# Main.net
KiCad netlist of a schematic drawn in Altium Designer
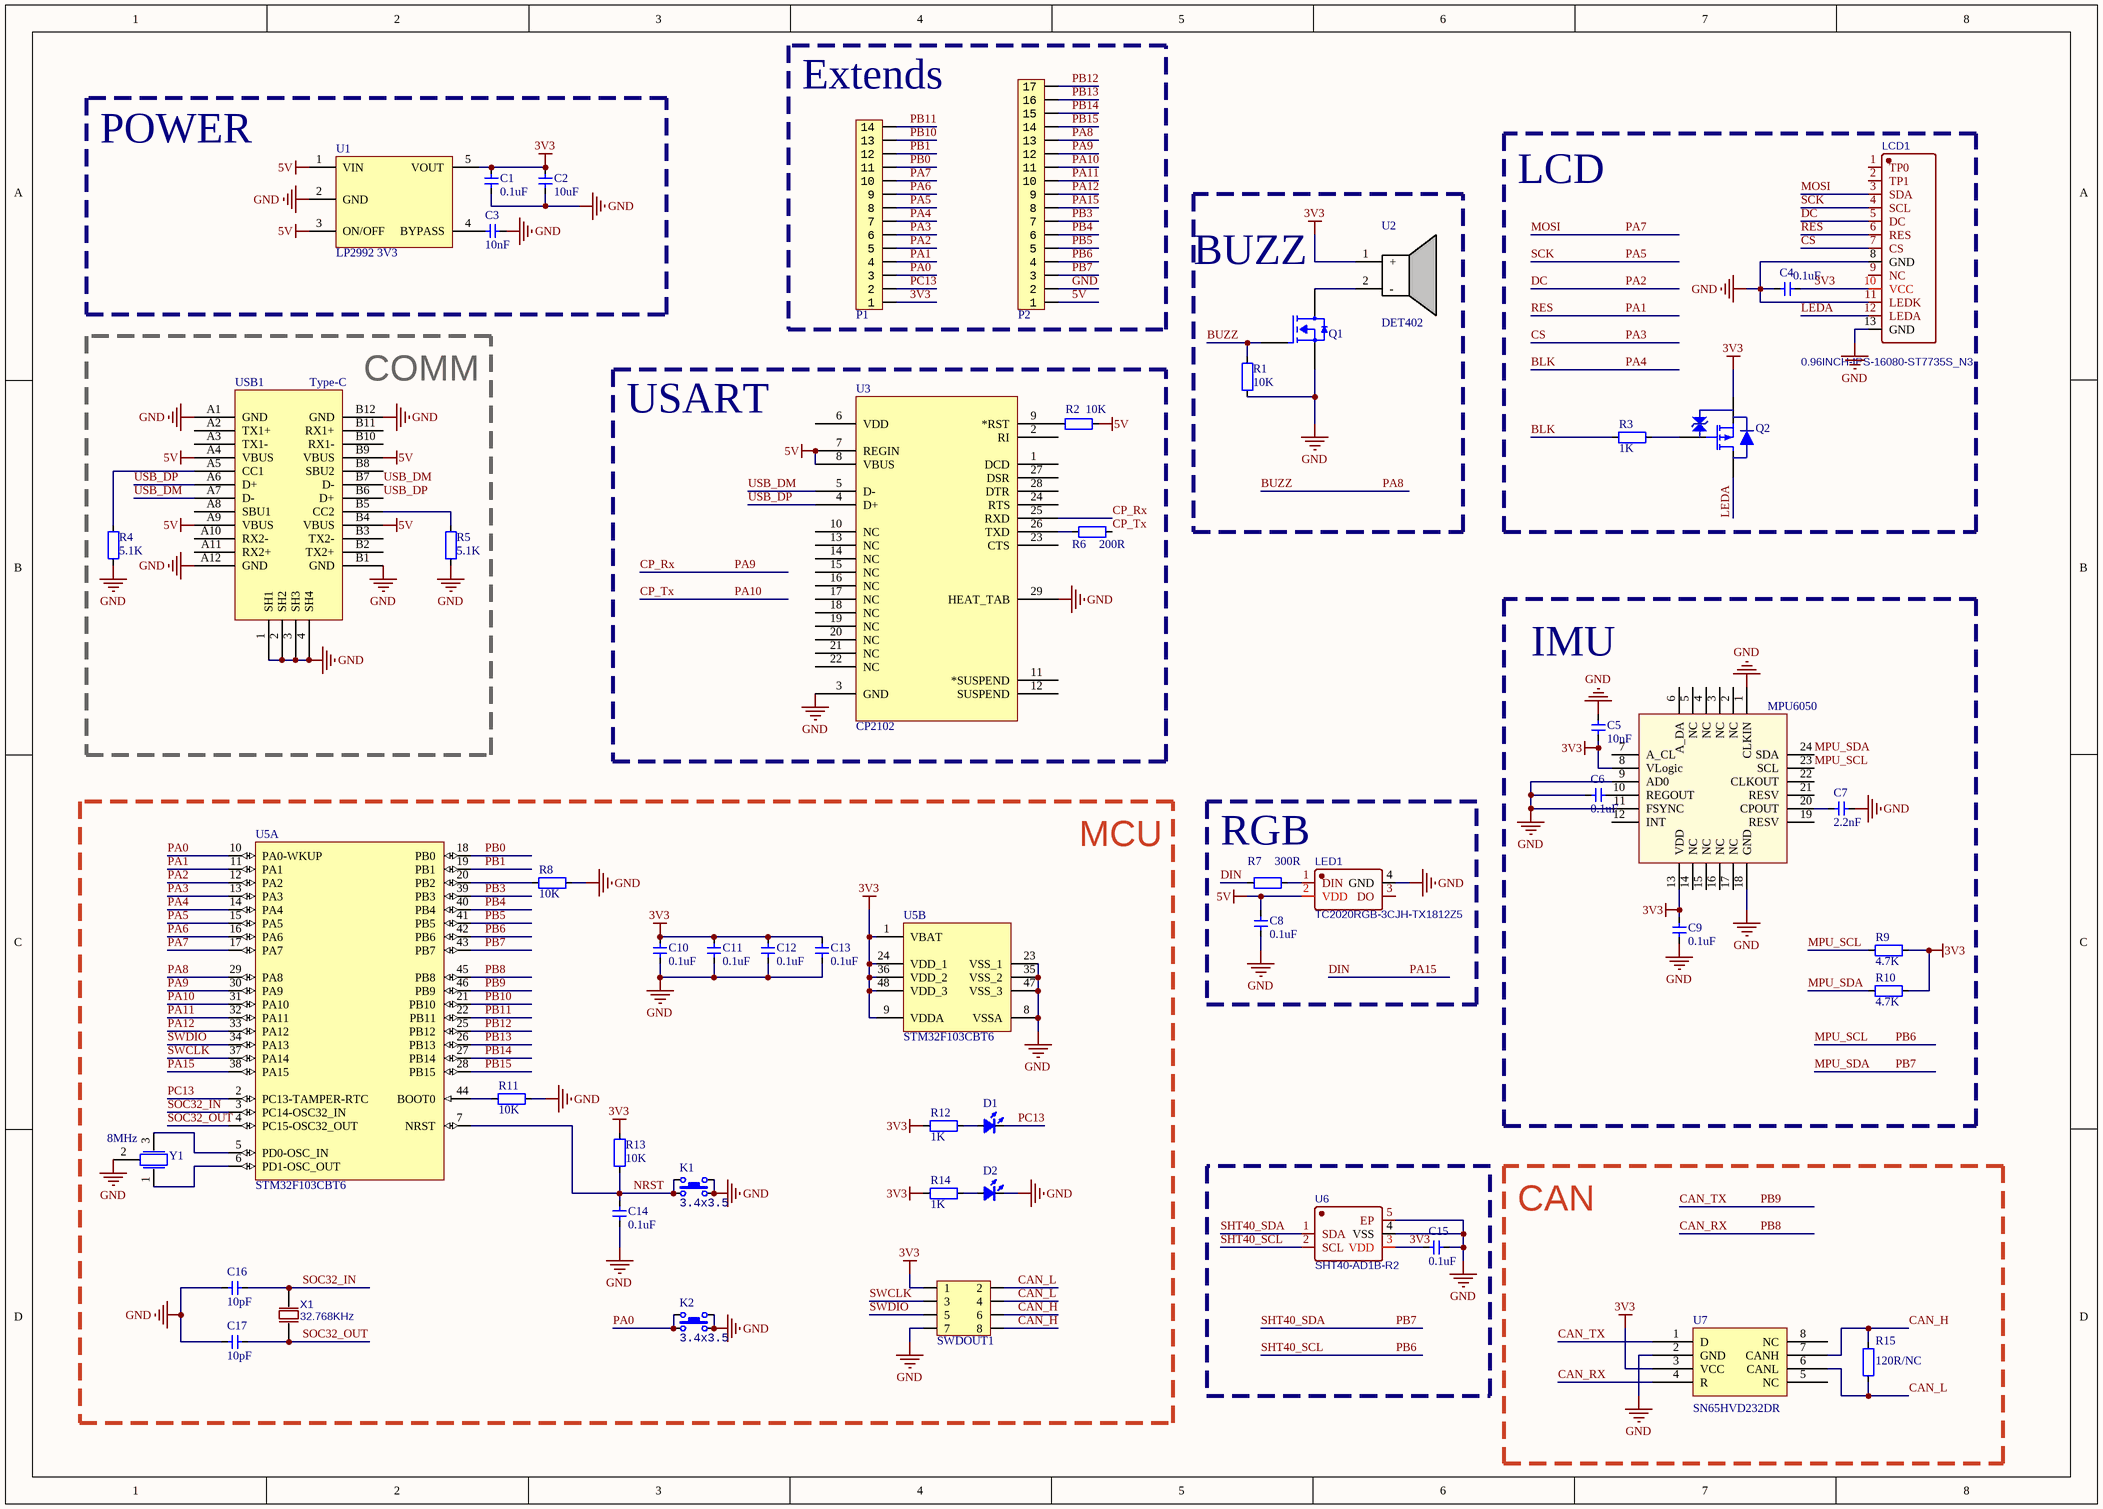
[diagram p0: Main.SchDoc]

(export (version "E")
  (design (tool "Eeschema 10.0.6"))
  (components
    (comp (ref "C1")
      (value "0.1uF")
      (footprint "CAP_0402")
      (description "Capacitor")
      (libsource (lib "MyPcbLib") (part "电容-0402"))
    )
    (comp (ref "C2")
      (value "10uF")
      (footprint "CAP_0402")
      (description "Capacitor")
      (libsource (lib "MyPcbLib") (part "电容-0402"))
    )
    (comp (ref "C3")
      (value "10nF")
      (footprint "CAP_0402")
      (description "Capacitor")
      (libsource (lib "MyPcbLib") (part "电容-0402"))
    )
    (comp (ref "C4")
      (value "0.1uF")
      (footprint "CAP_0402")
      (description "Capacitor")
      (libsource (lib "MyPcbLib") (part "电容-0402"))
    )
    (comp (ref "C5")
      (value "10nF")
      (footprint "CAP_0402")
      (description "Capacitor")
      (libsource (lib "MyPcbLib") (part "电容-0402"))
    )
    (comp (ref "C6")
      (value "0.1uF")
      (footprint "CAP_0402")
      (description "Capacitor")
      (libsource (lib "MyPcbLib") (part "电容-0402"))
    )
    (comp (ref "C7")
      (value "2.2nF")
      (footprint "CAP_0402")
      (description "Capacitor")
      (libsource (lib "MyPcbLib") (part "电容-0402"))
    )
    (comp (ref "C8")
      (value "0.1uF")
      (footprint "CAP_0402")
      (description "Capacitor")
      (libsource (lib "MyPcbLib") (part "电容-0402"))
    )
    (comp (ref "C9")
      (value "0.1uF")
      (footprint "CAP_0402")
      (description "Capacitor")
      (libsource (lib "MyPcbLib") (part "电容-0402"))
    )
    (comp (ref "C10")
      (value "0.1uF")
      (footprint "CAP_0402")
      (description "Capacitor")
      (libsource (lib "MyPcbLib") (part "电容-0402"))
    )
    (comp (ref "C11")
      (value "0.1uF")
      (footprint "CAP_0402")
      (description "Capacitor")
      (libsource (lib "MyPcbLib") (part "电容-0402"))
    )
    (comp (ref "C12")
      (value "0.1uF")
      (footprint "CAP_0402")
      (description "Capacitor")
      (libsource (lib "MyPcbLib") (part "电容-0402"))
    )
    (comp (ref "C13")
      (value "0.1uF")
      (footprint "CAP_0402")
      (description "Capacitor")
      (libsource (lib "MyPcbLib") (part "电容-0402"))
    )
    (comp (ref "C14")
      (value "0.1uF")
      (footprint "CAP_0402")
      (description "Capacitor")
      (libsource (lib "MyPcbLib") (part "电容-0402"))
    )
    (comp (ref "C15")
      (value "0.1uF")
      (footprint "CAP_0402")
      (description "Capacitor")
      (libsource (lib "MyPcbLib") (part "电容-0402"))
    )
    (comp (ref "C16")
      (value "10pF")
      (footprint "CAP_0402")
      (description "Capacitor")
      (libsource (lib "MyPcbLib") (part "电容-0402"))
    )
    (comp (ref "C17")
      (value "10pF")
      (footprint "CAP_0402")
      (description "Capacitor")
      (libsource (lib "MyPcbLib") (part "电容-0402"))
    )
    (comp (ref "D1")
      (value "color?")
      (footprint "LED_0402_RED")
      (description "LED")
      (libsource (lib "KitSprout") (part "LED_0402"))
    )
    (comp (ref "D2")
      (value "color?")
      (footprint "LED_0402_RED")
      (description "LED")
      (libsource (lib "KitSprout") (part "LED_0402"))
    )
    (comp (ref "K1")
      (value "3.4x3.5")
      (footprint "ButtonTACT_3.5*3.55_90")
      (description "Button")
      (fields (field (name "Comment") "TACT 4P"))
      (libsource (lib "KitSprout") (part "ButtonTACT"))
    )
    (comp (ref "K2")
      (value "3.4x3.5")
      (footprint "ButtonTACT_3.5*3.55_90")
      (description "Button")
      (fields (field (name "Comment") "TACT 4P"))
      (libsource (lib "KitSprout") (part "ButtonTACT"))
    )
    (comp (ref "LCD1")
      (value "0.96INCH-IPS-16080-ST7735S_N3")
      (footprint "LCD-0.96INCH-IPS-TFT-16080-ST7735S")
      (fields (field (name "CONTRIBUTOR") "micespring"))
      (libsource (lib "0.96 TFT") (part "0.96INCH-IPS-16080-ST7735S_N3"))
    )
    (comp (ref "LED1")
      (value "TC2020RGB-3CJH-TX1812Z5")
      (footprint "LED-SMD_4P-L2.1-W2.1-TL_TC2020RGB")
      (fields (field (name "BOM_SUPPLIER PART") "C784564") (field (name "CONTRIBUTOR") "LCSC"))
      (libsource (lib "GraduationProject") (part "TC2020RGB-3CJH-TX1812Z5"))
    )
    (comp (ref "P1")
      (value "HDR1x14_2.54")
      (footprint "HDR1X14_2.54_180")
      (description "Header")
      (libsource (lib "ESP32-PicoDK 12") (part "HDR1x14_2.54"))
    )
    (comp (ref "P2")
      (value "HDR1x17_2.54")
      (footprint "HDR1X17_2.54_180")
      (description "Header")
      (libsource (lib "ESP32-PicoDK") (part "HDR1x17_2.54"))
    )
    (comp (ref "Q1")
      (value "AO3400A")
      (footprint "SOT23-3")
      (description "N-MOS")
      (libsource (lib "Controller") (part "AO3400A"))
    )
    (comp (ref "Q2")
      (value "AO3415A")
      (footprint "SOT23-3")
      (description "MOSFET")
      (fields (field (name "PUBLISHER") "Altium Limited"))
      (libsource (lib "ExtendBoard") (part "AO3415A"))
    )
    (comp (ref "R1")
      (value "10K")
      (footprint "RES_0402")
      (description "Resistor")
      (libsource (lib "") (part "电阻-0402_3"))
    )
    (comp (ref "R2")
      (value "10K")
      (footprint "RES_0402")
      (description "Resistor")
      (libsource (lib "MyPcbLib") (part "电阻-0402"))
    )
    (comp (ref "R3")
      (value "1K")
      (footprint "RES_0402")
      (description "Resistor")
      (libsource (lib "") (part "电阻-0402_2"))
    )
    (comp (ref "R4")
      (value "5.1K")
      (footprint "RES_0402")
      (description "Resistor")
      (libsource (lib "") (part "电阻-0402_1"))
    )
    (comp (ref "R5")
      (value "5.1K")
      (footprint "RES_0402")
      (description "Resistor")
      (libsource (lib "") (part "电阻-0402_1"))
    )
    (comp (ref "R6")
      (value "200R")
      (footprint "RES_0402")
      (description "Resistor")
      (libsource (lib "MyPcbLib") (part "电阻-0402"))
    )
    (comp (ref "R7")
      (value "300R")
      (footprint "RES_0402")
      (description "Resistor")
      (libsource (lib "MyPcbLib") (part "电阻-0402"))
    )
    (comp (ref "R8")
      (value "10K")
      (footprint "RES_0402")
      (description "Resistor")
      (libsource (lib "MyPcbLib") (part "电阻-0402"))
    )
    (comp (ref "R9")
      (value "4.7K")
      (footprint "RES_0402")
      (description "Resistor")
      (libsource (lib "") (part "电阻-0402_2"))
    )
    (comp (ref "R10")
      (value "4.7K")
      (footprint "RES_0402")
      (description "Resistor")
      (libsource (lib "") (part "电阻-0402_2"))
    )
    (comp (ref "R11")
      (value "10K")
      (footprint "RES_0402")
      (description "Resistor")
      (libsource (lib "MyPcbLib") (part "电阻-0402"))
    )
    (comp (ref "R12")
      (value "1K")
      (footprint "RES_0402")
      (description "Resistor")
      (libsource (lib "") (part "电阻-0402_2"))
    )
    (comp (ref "R13")
      (value "10K")
      (footprint "RES_0402")
      (description "Resistor")
      (libsource (lib "") (part "电阻-0402_3"))
    )
    (comp (ref "R14")
      (value "1K")
      (footprint "RES_0402")
      (description "Resistor")
      (libsource (lib "") (part "电阻-0402_2"))
    )
    (comp (ref "R15")
      (value "120R/NC")
      (footprint "RES_0402")
      (description "Resistor")
      (libsource (lib "") (part "电阻-0402_1"))
    )
    (comp (ref "SWDOUT1")
      (value "HDR2x4_2.54")
      (footprint "HDR2X4_2.54_180H")
      (description "Header")
      (libsource (lib "ST-Link") (part "HDR2x4_2.54"))
    )
    (comp (ref "U1")
      (value "LP2992 3V3")
      (footprint "SOT23-5")
      (description "LDO")
      (libsource (lib "MyPcbLib") (part "LP2992"))
    )
    (comp (ref "U2") (value "DET402") (footprint "DET402") (libsource (lib "Controller") (part "DET402")))
    (comp (ref "U3")
      (value "CP2102")
      (footprint "QFN-28")
      (description "USB转TTL")
      (libsource (lib "mLib") (part "CP2102"))
    )
    (comp (ref "U4")
      (value "MPU6050")
      (footprint "QFN-24")
      (description "六轴传感器")
      (libsource (lib "mLib") (part "MPU6050"))
    )
    (comp (ref "U5")
      (value "STM32F103CBT6")
      (footprint "LQFP-48")
      (libsource (lib "STMicroelectronics STM32 F1") (part "STM32F103CBT6"))
    )
    (comp (ref "U6")
      (value "SHT40-AD1B-R2")
      (footprint "DFN-4_L1.5-W1.5-P0.8")
      (fields (field (name "BOM_SUPPLIER PART") "C2909890") (field (name "CONTRIBUTOR") "LCSC"))
      (libsource (lib "GraduationProject") (part "SHT40-AD1B-R2"))
    )
    (comp (ref "U7")
      (value "SN65HVD232D")
      (footprint "SO-8")
      (fields
        (field (name "MANUFACTURER") "Texas Instruments")
        (field (name "MANUFACTURER PART NUMBER") "SN65HVD232DR")
      )
      (libsource (lib "MyPcbLib") (part "SN65HVD232D"))
    )
    (comp (ref "USB1")
      (value "Type-C")
      (footprint "Type-C-TOP")
      (libsource (lib "MyPcbLib") (part "USB-Type-C-TOP"))
    )
    (comp (ref "X1")
      (value "32.768KHz")
      (footprint "OSC-SMD_L3.2-W1.5")
      (fields
        (field (name "BOM_SUPPLIER PART") "C280830")
        (field (name "BOM_MANUFACTURER PART") "EXS00A-MU00202")
        (field (name "CONTRIBUTOR") "LCSC")
      )
      (libsource (lib "GraduationProject") (part "32.768KHz"))
    )
    (comp (ref "Y1")
      (value "8MHz")
      (footprint "晶振-3P")
      (description "村田贴片")
      (libsource (lib "MyPcbLib") (part "晶振-3Pin"))
    )
  )
  (nets
    (net (code "1") (name "/BLK") (class "Default")
      (node (ref "P1") (pin "7") (pinfunction "7_7") (pintype "passive"))
      (node (ref "R3") (pin "1") (pinfunction "1_1") (pintype "passive"))
      (node (ref "U5") (pin "14") (pinfunction "PA4_14") (pintype "bidirectional"))
    )
    (net (code "2") (name "/BUZZ") (class "Default")
      (node (ref "P2") (pin "13") (pinfunction "13_13") (pintype "passive"))
      (node (ref "Q1") (pin "1") (pinfunction "G_1") (pintype "passive"))
      (node (ref "R1") (pin "2") (pinfunction "2_2") (pintype "passive"))
      (node (ref "U5") (pin "29") (pinfunction "PA8_29") (pintype "bidirectional"))
    )
    (net (code "3") (name "/CAN_H") (class "Default")
      (node (ref "R15") (pin "1") (pinfunction "1_1") (pintype "passive"))
      (node (ref "SWDOUT1") (pin "6") (pinfunction "6_6") (pintype "passive"))
      (node (ref "SWDOUT1") (pin "8") (pinfunction "8_8") (pintype "passive"))
      (node (ref "U7") (pin "7") (pinfunction "CANH_7") (pintype "passive"))
    )
    (net (code "4") (name "/CAN_L") (class "Default")
      (node (ref "R15") (pin "2") (pinfunction "2_2") (pintype "passive"))
      (node (ref "SWDOUT1") (pin "2") (pinfunction "2_2") (pintype "passive"))
      (node (ref "SWDOUT1") (pin "4") (pinfunction "4_4") (pintype "passive"))
      (node (ref "U7") (pin "6") (pinfunction "CANL_6") (pintype "passive"))
    )
    (net (code "5") (name "/CAN_RX") (class "Default")
      (node (ref "U5") (pin "45") (pinfunction "PB8_45") (pintype "bidirectional"))
      (node (ref "U7") (pin "4") (pinfunction "R_4") (pintype "passive"))
    )
    (net (code "6") (name "/CAN_TX") (class "Default")
      (node (ref "U5") (pin "46") (pinfunction "PB9_46") (pintype "bidirectional"))
      (node (ref "U7") (pin "1") (pinfunction "D_1") (pintype "passive"))
    )
    (net (code "7") (name "/CP_Rx") (class "Default")
      (node (ref "P2") (pin "12") (pinfunction "12_12") (pintype "passive"))
      (node (ref "U3") (pin "25") (pinfunction "RXD_25") (pintype "passive"))
      (node (ref "U5") (pin "30") (pinfunction "PA9_30") (pintype "bidirectional"))
    )
    (net (code "8") (name "/CP_Tx") (class "Default")
      (node (ref "P2") (pin "11") (pinfunction "11_11") (pintype "passive"))
      (node (ref "R6") (pin "1") (pinfunction "1_1") (pintype "passive"))
      (node (ref "U5") (pin "31") (pinfunction "PA10_31") (pintype "bidirectional"))
    )
    (net (code "9") (name "/CS") (class "Default")
      (node (ref "LCD1") (pin "7") (pinfunction "CS_7") (pintype "passive"))
      (node (ref "P1") (pin "6") (pinfunction "6_6") (pintype "passive"))
      (node (ref "U5") (pin "13") (pinfunction "PA3_13") (pintype "bidirectional"))
    )
    (net (code "10") (name "/DC") (class "Default")
      (node (ref "LCD1") (pin "5") (pinfunction "DC_5") (pintype "passive"))
      (node (ref "P1") (pin "5") (pinfunction "5_5") (pintype "passive"))
      (node (ref "U5") (pin "12") (pinfunction "PA2_12") (pintype "bidirectional"))
    )
    (net (code "11") (name "/DIN") (class "Default")
      (node (ref "P2") (pin "8") (pinfunction "8_8") (pintype "passive"))
      (node (ref "R7") (pin "2") (pinfunction "2_2") (pintype "passive"))
      (node (ref "U5") (pin "38") (pinfunction "PA15_38") (pintype "bidirectional"))
    )
    (net (code "12") (name "/LEDA") (class "Default")
      (node (ref "LCD1") (pin "12") (pinfunction "LEDA_12") (pintype "passive"))
      (node (ref "Q2") (pin "3") (pinfunction "D_3") (pintype "passive"))
    )
    (net (code "13") (name "/MOSI") (class "Default")
      (node (ref "LCD1") (pin "3") (pinfunction "SDA_3") (pintype "passive"))
      (node (ref "P1") (pin "10") (pinfunction "10_10") (pintype "passive"))
      (node (ref "U5") (pin "17") (pinfunction "PA7_17") (pintype "bidirectional"))
    )
    (net (code "14") (name "/MPU_SCL") (class "Default")
      (node (ref "P2") (pin "4") (pinfunction "4_4") (pintype "passive"))
      (node (ref "R9") (pin "1") (pinfunction "1_1") (pintype "passive"))
      (node (ref "U4") (pin "23") (pinfunction "SCL_23") (pintype "passive"))
      (node (ref "U5") (pin "42") (pinfunction "PB6_42") (pintype "bidirectional"))
      (node (ref "U6") (pin "2") (pinfunction "SCL_2") (pintype "passive"))
    )
    (net (code "15") (name "/MPU_SDA") (class "Default")
      (node (ref "P2") (pin "3") (pinfunction "3_3") (pintype "passive"))
      (node (ref "R10") (pin "1") (pinfunction "1_1") (pintype "passive"))
      (node (ref "U4") (pin "24") (pinfunction "SDA_24") (pintype "passive"))
      (node (ref "U5") (pin "43") (pinfunction "PB7_43") (pintype "bidirectional"))
      (node (ref "U6") (pin "1") (pinfunction "SDA_1") (pintype "passive"))
    )
    (net (code "16") (name "/NRST") (class "Default")
      (node (ref "C14") (pin "2") (pinfunction "2_2") (pintype "passive"))
      (node (ref "K1") (pin "1") (pinfunction "1_1") (pintype "passive"))
      (node (ref "K1") (pin "3") (pinfunction "3_3") (pintype "passive"))
      (node (ref "R13") (pin "1") (pinfunction "1_1") (pintype "passive"))
      (node (ref "U5") (pin "7") (pinfunction "NRST_7") (pintype "bidirectional"))
    )
    (net (code "17") (name "/PA0") (class "Default")
      (node (ref "K2") (pin "1") (pinfunction "1_1") (pintype "passive"))
      (node (ref "K2") (pin "3") (pinfunction "3_3") (pintype "passive"))
      (node (ref "P1") (pin "3") (pinfunction "3_3") (pintype "passive"))
      (node (ref "U5") (pin "10") (pinfunction "PA0-WKUP_10") (pintype "bidirectional"))
    )
    (net (code "18") (name "/PA1") (class "Default")
      (node (ref "LCD1") (pin "6") (pinfunction "RES_6") (pintype "passive"))
      (node (ref "P1") (pin "4") (pinfunction "4_4") (pintype "passive"))
      (node (ref "U5") (pin "11") (pinfunction "PA1_11") (pintype "bidirectional"))
    )
    (net (code "19") (name "/PA5") (class "Default")
      (node (ref "LCD1") (pin "4") (pinfunction "SCL_4") (pintype "passive"))
      (node (ref "P1") (pin "8") (pinfunction "8_8") (pintype "passive"))
      (node (ref "U5") (pin "15") (pinfunction "PA5_15") (pintype "bidirectional"))
    )
    (net (code "20") (name "/PA6") (class "Default")
      (node (ref "P1") (pin "9") (pinfunction "9_9") (pintype "passive"))
      (node (ref "U5") (pin "16") (pinfunction "PA6_16") (pintype "bidirectional"))
    )
    (net (code "21") (name "/PA11") (class "Default")
      (node (ref "P2") (pin "10") (pinfunction "10_10") (pintype "passive"))
      (node (ref "U5") (pin "32") (pinfunction "PA11_32") (pintype "bidirectional"))
    )
    (net (code "22") (name "/PA12") (class "Default")
      (node (ref "P2") (pin "9") (pinfunction "9_9") (pintype "passive"))
      (node (ref "U5") (pin "33") (pinfunction "PA12_33") (pintype "bidirectional"))
    )
    (net (code "23") (name "/PB0") (class "Default")
      (node (ref "P1") (pin "11") (pinfunction "11_11") (pintype "passive"))
      (node (ref "U5") (pin "18") (pinfunction "PB0_18") (pintype "bidirectional"))
    )
    (net (code "24") (name "/PB1") (class "Default")
      (node (ref "P1") (pin "12") (pinfunction "12_12") (pintype "passive"))
      (node (ref "U5") (pin "19") (pinfunction "PB1_19") (pintype "bidirectional"))
    )
    (net (code "25") (name "/PB3") (class "Default")
      (node (ref "P2") (pin "7") (pinfunction "7_7") (pintype "passive"))
      (node (ref "U5") (pin "39") (pinfunction "PB3_39") (pintype "bidirectional"))
    )
    (net (code "26") (name "/PB4") (class "Default")
      (node (ref "P2") (pin "6") (pinfunction "6_6") (pintype "passive"))
      (node (ref "U5") (pin "40") (pinfunction "PB4_40") (pintype "bidirectional"))
    )
    (net (code "27") (name "/PB5") (class "Default")
      (node (ref "P2") (pin "5") (pinfunction "5_5") (pintype "passive"))
      (node (ref "U5") (pin "41") (pinfunction "PB5_41") (pintype "bidirectional"))
    )
    (net (code "28") (name "/PB10") (class "Default")
      (node (ref "P1") (pin "13") (pinfunction "13_13") (pintype "passive"))
      (node (ref "U5") (pin "21") (pinfunction "PB10_21") (pintype "bidirectional"))
    )
    (net (code "29") (name "/PB11") (class "Default")
      (node (ref "P1") (pin "14") (pinfunction "14_14") (pintype "passive"))
      (node (ref "U5") (pin "22") (pinfunction "PB11_22") (pintype "bidirectional"))
    )
    (net (code "30") (name "/PB12") (class "Default")
      (node (ref "P2") (pin "17") (pinfunction "17_17") (pintype "passive"))
      (node (ref "U5") (pin "25") (pinfunction "PB12_25") (pintype "bidirectional"))
    )
    (net (code "31") (name "/PB13") (class "Default")
      (node (ref "P2") (pin "16") (pinfunction "16_16") (pintype "passive"))
      (node (ref "U5") (pin "26") (pinfunction "PB13_26") (pintype "bidirectional"))
    )
    (net (code "32") (name "/PB14") (class "Default")
      (node (ref "P2") (pin "15") (pinfunction "15_15") (pintype "passive"))
      (node (ref "U5") (pin "27") (pinfunction "PB14_27") (pintype "bidirectional"))
    )
    (net (code "33") (name "/PB15") (class "Default")
      (node (ref "P2") (pin "14") (pinfunction "14_14") (pintype "passive"))
      (node (ref "U5") (pin "28") (pinfunction "PB15_28") (pintype "bidirectional"))
    )
    (net (code "34") (name "/PC13") (class "Default")
      (node (ref "D1") (pin "2") (pinfunction "K_2") (pintype "passive"))
      (node (ref "P1") (pin "2") (pinfunction "2_2") (pintype "passive"))
      (node (ref "U5") (pin "2") (pinfunction "PC13-TAMPER-RTC_2") (pintype "bidirectional"))
    )
    (net (code "35") (name "/SOC32_IN") (class "Default")
      (node (ref "C16") (pin "1") (pinfunction "1_1") (pintype "passive"))
      (node (ref "U5") (pin "3") (pinfunction "PC14-OSC32_IN_3") (pintype "bidirectional"))
      (node (ref "X1") (pin "2") (pinfunction "OSC2_2") (pintype "passive"))
    )
    (net (code "36") (name "/SOC32_OUT") (class "Default")
      (node (ref "C17") (pin "1") (pinfunction "1_1") (pintype "passive"))
      (node (ref "U5") (pin "4") (pinfunction "PC15-OSC32_OUT_4") (pintype "bidirectional"))
      (node (ref "X1") (pin "1") (pinfunction "OSC1_1") (pintype "passive"))
    )
    (net (code "37") (name "/SWCLK") (class "Default")
      (node (ref "SWDOUT1") (pin "3") (pinfunction "3_3") (pintype "passive"))
      (node (ref "U5") (pin "37") (pinfunction "PA14_37") (pintype "bidirectional"))
    )
    (net (code "38") (name "/SWDIO") (class "Default")
      (node (ref "SWDOUT1") (pin "5") (pinfunction "5_5") (pintype "passive"))
      (node (ref "U5") (pin "34") (pinfunction "PA13_34") (pintype "bidirectional"))
    )
    (net (code "39") (name "/USB_DM") (class "Default")
      (node (ref "U3") (pin "5") (pinfunction "D-_5") (pintype "passive"))
      (node (ref "USB1") (pin "A7") (pinfunction "D-_A7") (pintype "passive"))
      (node (ref "USB1") (pin "B7") (pinfunction "D-_B7") (pintype "passive"))
    )
    (net (code "40") (name "/USB_DP") (class "Default")
      (node (ref "U3") (pin "4") (pinfunction "D+_4") (pintype "passive"))
      (node (ref "USB1") (pin "A6") (pinfunction "D+_A6") (pintype "passive"))
      (node (ref "USB1") (pin "B6") (pinfunction "D+_B6") (pintype "passive"))
    )
    (net (code "41") (name "3V3") (class "Default")
      (node (ref "C1") (pin "2") (pinfunction "2_2") (pintype "passive"))
      (node (ref "C10") (pin "2") (pinfunction "2_2") (pintype "passive"))
      (node (ref "C11") (pin "2") (pinfunction "2_2") (pintype "passive"))
      (node (ref "C12") (pin "2") (pinfunction "2_2") (pintype "passive"))
      (node (ref "C13") (pin "2") (pinfunction "2_2") (pintype "passive"))
      (node (ref "C15") (pin "2") (pinfunction "2_2") (pintype "passive"))
      (node (ref "C2") (pin "2") (pinfunction "2_2") (pintype "passive"))
      (node (ref "C4") (pin "1") (pinfunction "1_1") (pintype "passive"))
      (node (ref "C5") (pin "1") (pinfunction "1_1") (pintype "passive"))
      (node (ref "C9") (pin "2") (pinfunction "2_2") (pintype "passive"))
      (node (ref "LCD1") (pin "10") (pinfunction "VCC_10") (pintype "passive"))
      (node (ref "P1") (pin "1") (pinfunction "1_1") (pintype "passive"))
      (node (ref "Q2") (pin "2") (pinfunction "S_2") (pintype "passive"))
      (node (ref "R10") (pin "2") (pinfunction "2_2") (pintype "passive"))
      (node (ref "R12") (pin "1") (pinfunction "1_1") (pintype "passive"))
      (node (ref "R13") (pin "2") (pinfunction "2_2") (pintype "passive"))
      (node (ref "R14") (pin "1") (pinfunction "1_1") (pintype "passive"))
      (node (ref "R9") (pin "2") (pinfunction "2_2") (pintype "passive"))
      (node (ref "SWDOUT1") (pin "1") (pinfunction "1_1") (pintype "passive"))
      (node (ref "U1") (pin "5") (pinfunction "VOUT_5") (pintype "passive"))
      (node (ref "U2") (pin "1") (pinfunction "+_1") (pintype "passive"))
      (node (ref "U4") (pin "13") (pinfunction "VDD_13") (pintype "passive"))
      (node (ref "U4") (pin "8") (pinfunction "VLogic_8") (pintype "passive"))
      (node (ref "U5") (pin "1") (pinfunction "VBAT_1") (pintype "power_in"))
      (node (ref "U5") (pin "24") (pinfunction "VDD_1_24") (pintype "power_in"))
      (node (ref "U5") (pin "36") (pinfunction "VDD_2_36") (pintype "power_in"))
      (node (ref "U5") (pin "48") (pinfunction "VDD_3_48") (pintype "power_in"))
      (node (ref "U5") (pin "9") (pinfunction "VDDA_9") (pintype "power_in"))
      (node (ref "U6") (pin "3") (pinfunction "VDD_3") (pintype "passive"))
      (node (ref "U7") (pin "3") (pinfunction "VCC_3") (pintype "passive"))
    )
    (net (code "42") (name "5V") (class "Default")
      (node (ref "C8") (pin "1") (pinfunction "1_1") (pintype "passive"))
      (node (ref "LED1") (pin "2") (pinfunction "VDD_2") (pintype "passive"))
      (node (ref "P2") (pin "1") (pinfunction "1_1") (pintype "passive"))
      (node (ref "R2") (pin "1") (pinfunction "1_1") (pintype "passive"))
      (node (ref "U1") (pin "1") (pinfunction "VIN_1") (pintype "passive"))
      (node (ref "U1") (pin "3") (pinfunction "ON/OFF_3") (pintype "passive"))
      (node (ref "U3") (pin "7") (pinfunction "REGIN_7") (pintype "passive"))
      (node (ref "U3") (pin "8") (pinfunction "VBUS_8") (pintype "passive"))
      (node (ref "USB1") (pin "A4") (pinfunction "VBUS_A4") (pintype "passive"))
      (node (ref "USB1") (pin "A9") (pinfunction "VBUS_A9") (pintype "passive"))
      (node (ref "USB1") (pin "B4") (pinfunction "VBUS_B4") (pintype "passive"))
      (node (ref "USB1") (pin "B9") (pinfunction "VBUS_B9") (pintype "passive"))
    )
    (net (code "43") (name "GND") (class "Default")
      (node (ref "C1") (pin "1") (pinfunction "1_1") (pintype "passive"))
      (node (ref "C10") (pin "1") (pinfunction "1_1") (pintype "passive"))
      (node (ref "C11") (pin "1") (pinfunction "1_1") (pintype "passive"))
      (node (ref "C12") (pin "1") (pinfunction "1_1") (pintype "passive"))
      (node (ref "C13") (pin "1") (pinfunction "1_1") (pintype "passive"))
      (node (ref "C14") (pin "1") (pinfunction "1_1") (pintype "passive"))
      (node (ref "C15") (pin "1") (pinfunction "1_1") (pintype "passive"))
      (node (ref "C16") (pin "2") (pinfunction "2_2") (pintype "passive"))
      (node (ref "C17") (pin "2") (pinfunction "2_2") (pintype "passive"))
      (node (ref "C2") (pin "1") (pinfunction "1_1") (pintype "passive"))
      (node (ref "C3") (pin "1") (pinfunction "1_1") (pintype "passive"))
      (node (ref "C4") (pin "2") (pinfunction "2_2") (pintype "passive"))
      (node (ref "C5") (pin "2") (pinfunction "2_2") (pintype "passive"))
      (node (ref "C6") (pin "2") (pinfunction "2_2") (pintype "passive"))
      (node (ref "C7") (pin "1") (pinfunction "1_1") (pintype "passive"))
      (node (ref "C8") (pin "2") (pinfunction "2_2") (pintype "passive"))
      (node (ref "C9") (pin "1") (pinfunction "1_1") (pintype "passive"))
      (node (ref "D2") (pin "2") (pinfunction "K_2") (pintype "passive"))
      (node (ref "K1") (pin "2") (pinfunction "2_2") (pintype "passive"))
      (node (ref "K1") (pin "4") (pinfunction "4_4") (pintype "passive"))
      (node (ref "K2") (pin "2") (pinfunction "2_2") (pintype "passive"))
      (node (ref "K2") (pin "4") (pinfunction "4_4") (pintype "passive"))
      (node (ref "LCD1") (pin "11") (pinfunction "LEDK_11") (pintype "passive"))
      (node (ref "LCD1") (pin "13") (pinfunction "GND_13") (pintype "passive"))
      (node (ref "LCD1") (pin "8") (pinfunction "GND_8") (pintype "passive"))
      (node (ref "LED1") (pin "4") (pinfunction "GND_4") (pintype "passive"))
      (node (ref "P2") (pin "2") (pinfunction "2_2") (pintype "passive"))
      (node (ref "Q1") (pin "2") (pinfunction "S_2") (pintype "passive"))
      (node (ref "R1") (pin "1") (pinfunction "1_1") (pintype "passive"))
      (node (ref "R11") (pin "1") (pinfunction "1_1") (pintype "passive"))
      (node (ref "R4") (pin "2") (pinfunction "2_2") (pintype "passive"))
      (node (ref "R5") (pin "2") (pinfunction "2_2") (pintype "passive"))
      (node (ref "R8") (pin "1") (pinfunction "1_1") (pintype "passive"))
      (node (ref "SWDOUT1") (pin "7") (pinfunction "7_7") (pintype "passive"))
      (node (ref "U1") (pin "2") (pinfunction "GND_2") (pintype "passive"))
      (node (ref "U3") (pin "29") (pinfunction "HEAT_TAB_29") (pintype "passive"))
      (node (ref "U3") (pin "3") (pinfunction "GND_3") (pintype "passive"))
      (node (ref "U4") (pin "1") (pinfunction "CLKIN_1") (pintype "passive"))
      (node (ref "U4") (pin "11") (pinfunction "FSYNC_11") (pintype "passive"))
      (node (ref "U4") (pin "18") (pinfunction "GND_18") (pintype "passive"))
      (node (ref "U4") (pin "9") (pinfunction "AD0_9") (pintype "passive"))
      (node (ref "U5") (pin "23") (pinfunction "VSS_1_23") (pintype "power_in"))
      (node (ref "U5") (pin "35") (pinfunction "VSS_2_35") (pintype "power_in"))
      (node (ref "U5") (pin "47") (pinfunction "VSS_3_47") (pintype "power_in"))
      (node (ref "U5") (pin "8") (pinfunction "VSSA_8") (pintype "power_in"))
      (node (ref "U6") (pin "4") (pinfunction "VSS_4") (pintype "passive"))
      (node (ref "U6") (pin "5") (pinfunction "EP_5") (pintype "passive"))
      (node (ref "U7") (pin "2") (pinfunction "GND_2") (pintype "passive"))
      (node (ref "USB1") (pin "1") (pinfunction "SH1_1") (pintype "passive"))
      (node (ref "USB1") (pin "2") (pinfunction "SH2_2") (pintype "passive"))
      (node (ref "USB1") (pin "3") (pinfunction "SH3_3") (pintype "passive"))
      (node (ref "USB1") (pin "4") (pinfunction "SH4_4") (pintype "passive"))
      (node (ref "USB1") (pin "A1") (pinfunction "GND_A1") (pintype "passive"))
      (node (ref "USB1") (pin "A12") (pinfunction "GND_A12") (pintype "passive"))
      (node (ref "USB1") (pin "B1") (pinfunction "GND_B1") (pintype "passive"))
      (node (ref "USB1") (pin "B12") (pinfunction "GND_B12") (pintype "passive"))
      (node (ref "Y1") (pin "2") (pinfunction "2_2") (pintype "passive"))
    )
    (net (code "44") (name "Net-(D1-A)") (class "Default")
      (node (ref "D1") (pin "1") (pinfunction "A_1") (pintype "passive"))
      (node (ref "R12") (pin "2") (pinfunction "2_2") (pintype "passive"))
    )
    (net (code "45") (name "Net-(D2-A)") (class "Default")
      (node (ref "D2") (pin "1") (pinfunction "A_1") (pintype "passive"))
      (node (ref "R14") (pin "2") (pinfunction "2_2") (pintype "passive"))
    )
    (net (code "46") (name "Net-(LED1-DIN)") (class "Default")
      (node (ref "LED1") (pin "1") (pinfunction "DIN_1") (pintype "passive"))
      (node (ref "R7") (pin "1") (pinfunction "1_1") (pintype "passive"))
    )
    (net (code "47") (name "Net-(Q1-D)") (class "Default")
      (node (ref "Q1") (pin "3") (pinfunction "D_3") (pintype "passive"))
      (node (ref "U2") (pin "2") (pinfunction "-_2") (pintype "passive"))
    )
    (net (code "48") (name "Net-(Q2-G)") (class "Default")
      (node (ref "Q2") (pin "1") (pinfunction "G_1") (pintype "passive"))
      (node (ref "R3") (pin "2") (pinfunction "2_2") (pintype "passive"))
    )
    (net (code "49") (name "Net-(U1-BYPASS)") (class "Default")
      (node (ref "C3") (pin "2") (pinfunction "2_2") (pintype "passive"))
      (node (ref "U1") (pin "4") (pinfunction "BYPASS_4") (pintype "passive"))
    )
    (net (code "50") (name "Net-(U3-*RST)") (class "Default")
      (node (ref "R2") (pin "2") (pinfunction "2_2") (pintype "passive"))
      (node (ref "U3") (pin "9") (pinfunction "*RST_9") (pintype "passive"))
    )
    (net (code "51") (name "Net-(U3-TXD)") (class "Default")
      (node (ref "R6") (pin "2") (pinfunction "2_2") (pintype "passive"))
      (node (ref "U3") (pin "26") (pinfunction "TXD_26") (pintype "passive"))
    )
    (net (code "52") (name "Net-(U4-CPOUT)") (class "Default")
      (node (ref "C7") (pin "2") (pinfunction "2_2") (pintype "passive"))
      (node (ref "U4") (pin "20") (pinfunction "CPOUT_20") (pintype "passive"))
    )
    (net (code "53") (name "Net-(U4-REGOUT)") (class "Default")
      (node (ref "C6") (pin "1") (pinfunction "1_1") (pintype "passive"))
      (node (ref "U4") (pin "10") (pinfunction "REGOUT_10") (pintype "passive"))
    )
    (net (code "54") (name "Net-(U5A-BOOT0)") (class "Default")
      (node (ref "R11") (pin "2") (pinfunction "2_2") (pintype "passive"))
      (node (ref "U5") (pin "44") (pinfunction "BOOT0_44") (pintype "input"))
    )
    (net (code "55") (name "Net-(U5A-PB2)") (class "Default")
      (node (ref "R8") (pin "2") (pinfunction "2_2") (pintype "passive"))
      (node (ref "U5") (pin "20") (pinfunction "PB2_20") (pintype "bidirectional"))
    )
    (net (code "56") (name "Net-(U5A-PD0-OSC_IN)") (class "Default")
      (node (ref "U5") (pin "5") (pinfunction "PD0-OSC_IN_5") (pintype "bidirectional"))
      (node (ref "Y1") (pin "3") (pinfunction "3_3") (pintype "passive"))
    )
    (net (code "57") (name "Net-(U5A-PD1-OSC_OUT)") (class "Default")
      (node (ref "U5") (pin "6") (pinfunction "PD1-OSC_OUT_6") (pintype "bidirectional"))
      (node (ref "Y1") (pin "1") (pinfunction "1_1") (pintype "passive"))
    )
    (net (code "58") (name "Net-(USB1-CC1)") (class "Default")
      (node (ref "R4") (pin "1") (pinfunction "1_1") (pintype "passive"))
      (node (ref "USB1") (pin "A5") (pinfunction "CC1_A5") (pintype "passive"))
    )
    (net (code "59") (name "Net-(USB1-CC2)") (class "Default")
      (node (ref "R5") (pin "1") (pinfunction "1_1") (pintype "passive"))
      (node (ref "USB1") (pin "B5") (pinfunction "CC2_B5") (pintype "passive"))
    )
    (net (code "60") (name "unconnected-(LCD1-NC-Pad9)") (class "Default")
      (node (ref "LCD1") (pin "9") (pinfunction "NC_9") (pintype "passive"))
    )
    (net (code "61") (name "unconnected-(LCD1-TP0-Pad1)") (class "Default")
      (node (ref "LCD1") (pin "1") (pinfunction "TP0_1") (pintype "passive"))
    )
    (net (code "62") (name "unconnected-(LCD1-TP1-Pad2)") (class "Default")
      (node (ref "LCD1") (pin "2") (pinfunction "TP1_2") (pintype "passive"))
    )
    (net (code "63") (name "unconnected-(LED1-DO-Pad3)") (class "Default")
      (node (ref "LED1") (pin "3") (pinfunction "DO_3") (pintype "passive"))
    )
    (net (code "64") (name "unconnected-(U3-*SUSPEND-Pad11)") (class "Default")
      (node (ref "U3") (pin "11") (pinfunction "*SUSPEND_11") (pintype "passive"))
    )
    (net (code "65") (name "unconnected-(U3-CTS-Pad23)") (class "Default")
      (node (ref "U3") (pin "23") (pinfunction "CTS_23") (pintype "passive"))
    )
    (net (code "66") (name "unconnected-(U3-DCD-Pad1)") (class "Default")
      (node (ref "U3") (pin "1") (pinfunction "DCD_1") (pintype "passive"))
    )
    (net (code "67") (name "unconnected-(U3-DSR-Pad27)") (class "Default")
      (node (ref "U3") (pin "27") (pinfunction "DSR_27") (pintype "passive"))
    )
    (net (code "68") (name "unconnected-(U3-DTR-Pad28)") (class "Default")
      (node (ref "U3") (pin "28") (pinfunction "DTR_28") (pintype "passive"))
    )
    (net (code "69") (name "unconnected-(U3-NC-Pad10)") (class "Default")
      (node (ref "U3") (pin "10") (pinfunction "NC_10") (pintype "passive"))
    )
    (net (code "70") (name "unconnected-(U3-NC-Pad13)") (class "Default")
      (node (ref "U3") (pin "13") (pinfunction "NC_13") (pintype "passive"))
    )
    (net (code "71") (name "unconnected-(U3-NC-Pad14)") (class "Default")
      (node (ref "U3") (pin "14") (pinfunction "NC_14") (pintype "passive"))
    )
    (net (code "72") (name "unconnected-(U3-NC-Pad15)") (class "Default")
      (node (ref "U3") (pin "15") (pinfunction "NC_15") (pintype "passive"))
    )
    (net (code "73") (name "unconnected-(U3-NC-Pad16)") (class "Default")
      (node (ref "U3") (pin "16") (pinfunction "NC_16") (pintype "passive"))
    )
    (net (code "74") (name "unconnected-(U3-NC-Pad17)") (class "Default")
      (node (ref "U3") (pin "17") (pinfunction "NC_17") (pintype "passive"))
    )
    (net (code "75") (name "unconnected-(U3-NC-Pad18)") (class "Default")
      (node (ref "U3") (pin "18") (pinfunction "NC_18") (pintype "passive"))
    )
    (net (code "76") (name "unconnected-(U3-NC-Pad19)") (class "Default")
      (node (ref "U3") (pin "19") (pinfunction "NC_19") (pintype "passive"))
    )
    (net (code "77") (name "unconnected-(U3-NC-Pad20)") (class "Default")
      (node (ref "U3") (pin "20") (pinfunction "NC_20") (pintype "passive"))
    )
    (net (code "78") (name "unconnected-(U3-NC-Pad21)") (class "Default")
      (node (ref "U3") (pin "21") (pinfunction "NC_21") (pintype "passive"))
    )
    (net (code "79") (name "unconnected-(U3-NC-Pad22)") (class "Default")
      (node (ref "U3") (pin "22") (pinfunction "NC_22") (pintype "passive"))
    )
    (net (code "80") (name "unconnected-(U3-RI-Pad2)") (class "Default")
      (node (ref "U3") (pin "2") (pinfunction "RI_2") (pintype "passive"))
    )
    (net (code "81") (name "unconnected-(U3-RTS-Pad24)") (class "Default")
      (node (ref "U3") (pin "24") (pinfunction "RTS_24") (pintype "passive"))
    )
    (net (code "82") (name "unconnected-(U3-SUSPEND-Pad12)") (class "Default")
      (node (ref "U3") (pin "12") (pinfunction "SUSPEND_12") (pintype "passive"))
    )
    (net (code "83") (name "unconnected-(U3-VDD-Pad6)") (class "Default")
      (node (ref "U3") (pin "6") (pinfunction "VDD_6") (pintype "passive"))
    )
    (net (code "84") (name "unconnected-(U4-A_CL-Pad7)") (class "Default")
      (node (ref "U4") (pin "7") (pinfunction "A_CL_7") (pintype "passive"))
    )
    (net (code "85") (name "unconnected-(U4-A_DA-Pad6)") (class "Default")
      (node (ref "U4") (pin "6") (pinfunction "A_DA_6") (pintype "passive"))
    )
    (net (code "86") (name "unconnected-(U4-CLKOUT-Pad22)") (class "Default")
      (node (ref "U4") (pin "22") (pinfunction "CLKOUT_22") (pintype "passive"))
    )
    (net (code "87") (name "unconnected-(U4-INT-Pad12)") (class "Default")
      (node (ref "U4") (pin "12") (pinfunction "INT_12") (pintype "passive"))
    )
    (net (code "88") (name "unconnected-(U4-NC-Pad2)") (class "Default")
      (node (ref "U4") (pin "2") (pinfunction "NC_2") (pintype "passive"))
    )
    (net (code "89") (name "unconnected-(U4-NC-Pad3)") (class "Default")
      (node (ref "U4") (pin "3") (pinfunction "NC_3") (pintype "passive"))
    )
    (net (code "90") (name "unconnected-(U4-NC-Pad4)") (class "Default")
      (node (ref "U4") (pin "4") (pinfunction "NC_4") (pintype "passive"))
    )
    (net (code "91") (name "unconnected-(U4-NC-Pad5)") (class "Default")
      (node (ref "U4") (pin "5") (pinfunction "NC_5") (pintype "passive"))
    )
    (net (code "92") (name "unconnected-(U4-NC-Pad14)") (class "Default")
      (node (ref "U4") (pin "14") (pinfunction "NC_14") (pintype "passive"))
    )
    (net (code "93") (name "unconnected-(U4-NC-Pad15)") (class "Default")
      (node (ref "U4") (pin "15") (pinfunction "NC_15") (pintype "passive"))
    )
    (net (code "94") (name "unconnected-(U4-NC-Pad16)") (class "Default")
      (node (ref "U4") (pin "16") (pinfunction "NC_16") (pintype "passive"))
    )
    (net (code "95") (name "unconnected-(U4-NC-Pad17)") (class "Default")
      (node (ref "U4") (pin "17") (pinfunction "NC_17") (pintype "passive"))
    )
    (net (code "96") (name "unconnected-(U4-RESV-Pad19)") (class "Default")
      (node (ref "U4") (pin "19") (pinfunction "RESV_19") (pintype "passive"))
    )
    (net (code "97") (name "unconnected-(U4-RESV-Pad21)") (class "Default")
      (node (ref "U4") (pin "21") (pinfunction "RESV_21") (pintype "passive"))
    )
    (net (code "98") (name "unconnected-(U7-NC-Pad5)") (class "Default")
      (node (ref "U7") (pin "5") (pinfunction "NC_5") (pintype "passive"))
    )
    (net (code "99") (name "unconnected-(U7-NC-Pad8)") (class "Default")
      (node (ref "U7") (pin "8") (pinfunction "NC_8") (pintype "passive"))
    )
    (net (code "100") (name "unconnected-(USB1-RX1+-PadB11)") (class "Default")
      (node (ref "USB1") (pin "B11") (pinfunction "RX1+_B11") (pintype "passive"))
    )
    (net (code "101") (name "unconnected-(USB1-RX1--PadB10)") (class "Default")
      (node (ref "USB1") (pin "B10") (pinfunction "RX1-_B10") (pintype "passive"))
    )
    (net (code "102") (name "unconnected-(USB1-RX2+-PadA11)") (class "Default")
      (node (ref "USB1") (pin "A11") (pinfunction "RX2+_A11") (pintype "passive"))
    )
    (net (code "103") (name "unconnected-(USB1-RX2--PadA10)") (class "Default")
      (node (ref "USB1") (pin "A10") (pinfunction "RX2-_A10") (pintype "passive"))
    )
    (net (code "104") (name "unconnected-(USB1-SBU1-PadA8)") (class "Default")
      (node (ref "USB1") (pin "A8") (pinfunction "SBU1_A8") (pintype "passive"))
    )
    (net (code "105") (name "unconnected-(USB1-SBU2-PadB8)") (class "Default")
      (node (ref "USB1") (pin "B8") (pinfunction "SBU2_B8") (pintype "passive"))
    )
    (net (code "106") (name "unconnected-(USB1-TX1+-PadA2)") (class "Default")
      (node (ref "USB1") (pin "A2") (pinfunction "TX1+_A2") (pintype "passive"))
    )
    (net (code "107") (name "unconnected-(USB1-TX1--PadA3)") (class "Default")
      (node (ref "USB1") (pin "A3") (pinfunction "TX1-_A3") (pintype "passive"))
    )
    (net (code "108") (name "unconnected-(USB1-TX2+-PadB2)") (class "Default")
      (node (ref "USB1") (pin "B2") (pinfunction "TX2+_B2") (pintype "passive"))
    )
    (net (code "109") (name "unconnected-(USB1-TX2--PadB3)") (class "Default")
      (node (ref "USB1") (pin "B3") (pinfunction "TX2-_B3") (pintype "passive"))
    )
  )
)
